# RS232.net
KiCad netlist of a schematic drawn in Altium Designer
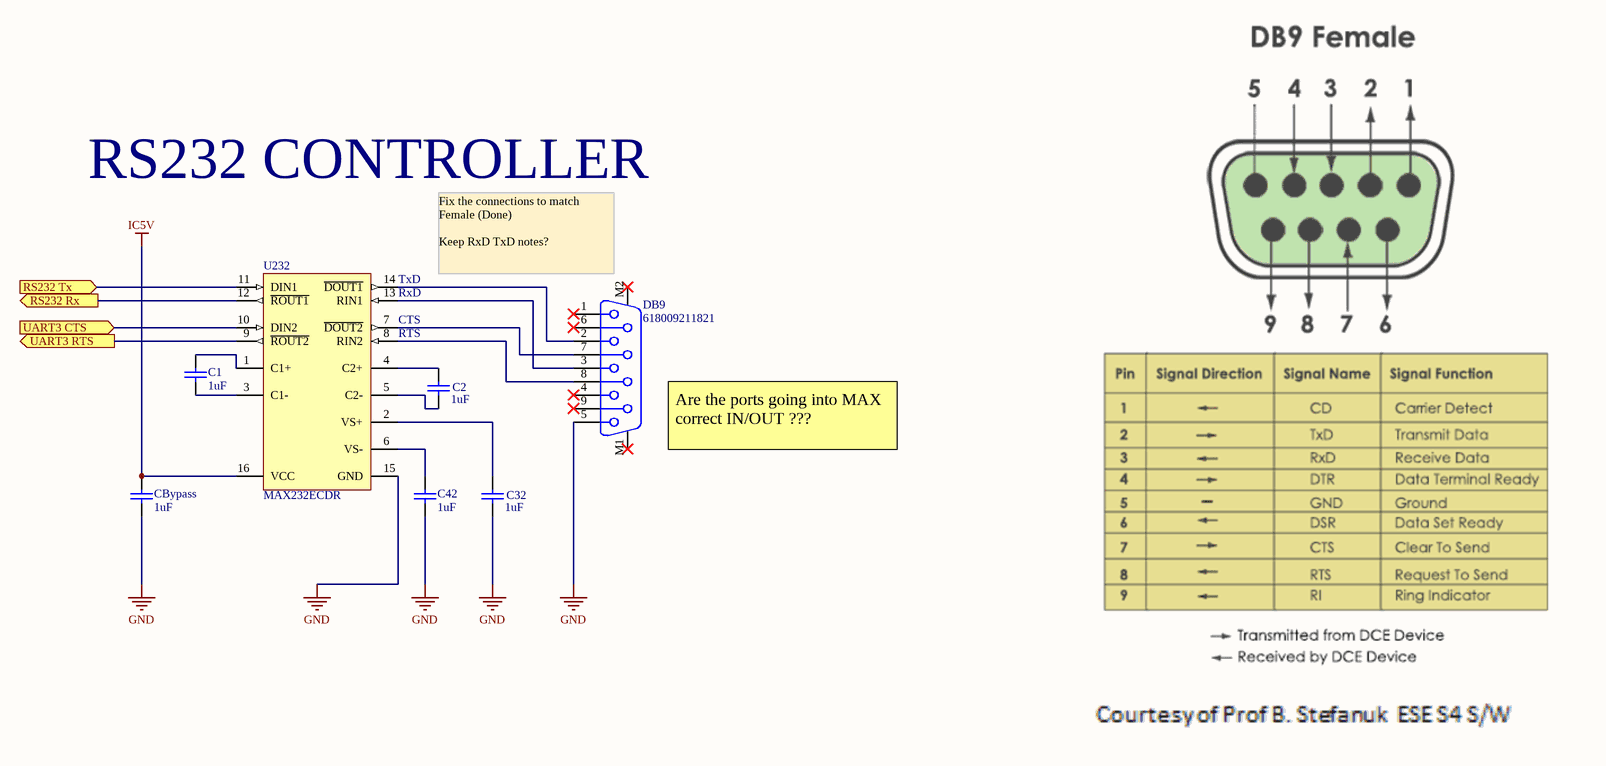
[diagram p0: RS232.SchDoc]

(export (version "E")
  (design (tool "Eeschema 10.0.6"))
  (components
    (comp (ref "C1")
      (value "1uF")
      (description "Capacitor")
      (libsource (lib "Simulation Generic Components") (part "Capacitor"))
    )
    (comp (ref "C2")
      (value "1uF")
      (description "Capacitor")
      (libsource (lib "Simulation Generic Components") (part "Capacitor"))
    )
    (comp (ref "C32")
      (value "1uF")
      (description "Capacitor")
      (libsource (lib "Simulation Generic Components") (part "Capacitor"))
    )
    (comp (ref "C42")
      (value "1uF")
      (description "Capacitor")
      (libsource (lib "Simulation Generic Components") (part "Capacitor"))
    )
    (comp (ref "CBypass")
      (value "1uF")
      (description "Capacitor")
      (libsource (lib "Simulation Generic Components") (part "Capacitor"))
    )
    (comp (ref "DB9")
      (value "618009211821")
      (footprint "618009211821")
      (libsource (lib "Altium Content Vault") (part "D-Sub_Female_09p"))
    )
    (comp (ref "U232")
      (value "MAX232ECDR")
      (footprint "D0016A_L")
      (libsource (lib "Altium Content Vault") (part "TI-MAX232E-SOIC_D-16"))
    )
  )
  (nets
    (net (code "1") (name "/RS232 Rx") (class "Default")
      (node (ref "U232") (pin "12") (pinfunction "~{ROUT1}_12") (pintype "output"))
    )
    (net (code "2") (name "/RS232 Tx") (class "Default")
      (node (ref "U232") (pin "11") (pinfunction "DIN1_11") (pintype "input"))
    )
    (net (code "3") (name "/UART3 CTS") (class "Default")
      (node (ref "U232") (pin "10") (pinfunction "DIN2_10") (pintype "input"))
    )
    (net (code "4") (name "/UART3 RTS") (class "Default")
      (node (ref "U232") (pin "9") (pinfunction "~{ROUT2}_9") (pintype "output"))
    )
    (net (code "5") (name "GND") (class "Default")
      (node (ref "C32") (pin "1") (pinfunction "1_1") (pintype "passive"))
      (node (ref "C42") (pin "1") (pinfunction "1_1") (pintype "passive"))
      (node (ref "CBypass") (pin "1") (pinfunction "1_1") (pintype "passive"))
      (node (ref "DB9") (pin "5") (pinfunction "5_5") (pintype "passive"))
      (node (ref "U232") (pin "15") (pinfunction "GND_15") (pintype "power_in"))
    )
    (net (code "6") (name "IC5V") (class "Default")
      (node (ref "CBypass") (pin "2") (pinfunction "2_2") (pintype "passive"))
      (node (ref "U232") (pin "16") (pinfunction "VCC_16") (pintype "power_in"))
    )
    (net (code "7") (name "Net-(U232-C1+)") (class "Default")
      (node (ref "C1") (pin "2") (pinfunction "2_2") (pintype "passive"))
      (node (ref "U232") (pin "1") (pinfunction "C1+_1") (pintype "passive"))
    )
    (net (code "8") (name "Net-(U232-C1-)") (class "Default")
      (node (ref "C1") (pin "1") (pinfunction "1_1") (pintype "passive"))
      (node (ref "U232") (pin "3") (pinfunction "C1-_3") (pintype "passive"))
    )
    (net (code "9") (name "Net-(U232-C2+)") (class "Default")
      (node (ref "C2") (pin "2") (pinfunction "2_2") (pintype "passive"))
      (node (ref "U232") (pin "4") (pinfunction "C2+_4") (pintype "passive"))
    )
    (net (code "10") (name "Net-(U232-C2-)") (class "Default")
      (node (ref "C2") (pin "1") (pinfunction "1_1") (pintype "passive"))
      (node (ref "U232") (pin "5") (pinfunction "C2-_5") (pintype "passive"))
    )
    (net (code "11") (name "Net-(U232-RIN1)") (class "Default")
      (node (ref "DB9") (pin "3") (pinfunction "3_3") (pintype "passive"))
      (node (ref "U232") (pin "13") (pinfunction "RIN1_13") (pintype "input"))
    )
    (net (code "12") (name "Net-(U232-RIN2)") (class "Default")
      (node (ref "DB9") (pin "8") (pinfunction "8_8") (pintype "passive"))
      (node (ref "U232") (pin "8") (pinfunction "RIN2_8") (pintype "input"))
    )
    (net (code "13") (name "Net-(U232-VS+)") (class "Default")
      (node (ref "C32") (pin "2") (pinfunction "2_2") (pintype "passive"))
      (node (ref "U232") (pin "2") (pinfunction "VS+_2") (pintype "power_in"))
    )
    (net (code "14") (name "Net-(U232-VS-)") (class "Default")
      (node (ref "C42") (pin "2") (pinfunction "2_2") (pintype "passive"))
      (node (ref "U232") (pin "6") (pinfunction "VS-_6") (pintype "power_in"))
    )
    (net (code "15") (name "Net-(U232-~{DOUT1})") (class "Default")
      (node (ref "DB9") (pin "2") (pinfunction "2_2") (pintype "passive"))
      (node (ref "U232") (pin "14") (pinfunction "~{DOUT1}_14") (pintype "output"))
    )
    (net (code "16") (name "Net-(U232-~{DOUT2})") (class "Default")
      (node (ref "DB9") (pin "7") (pinfunction "7_7") (pintype "passive"))
      (node (ref "U232") (pin "7") (pinfunction "~{DOUT2}_7") (pintype "output"))
    )
    (net (code "17") (name "unconnected-(DB9-Pad1)") (class "Default")
      (node (ref "DB9") (pin "1") (pinfunction "1_1") (pintype "passive+no_connect"))
    )
    (net (code "18") (name "unconnected-(DB9-Pad4)") (class "Default")
      (node (ref "DB9") (pin "4") (pinfunction "4_4") (pintype "passive+no_connect"))
    )
    (net (code "19") (name "unconnected-(DB9-Pad6)") (class "Default")
      (node (ref "DB9") (pin "6") (pinfunction "6_6") (pintype "passive+no_connect"))
    )
    (net (code "20") (name "unconnected-(DB9-Pad9)") (class "Default")
      (node (ref "DB9") (pin "9") (pinfunction "9_9") (pintype "passive+no_connect"))
    )
    (net (code "21") (name "unconnected-(DB9-PadM1)") (class "Default")
      (node (ref "DB9") (pin "M1") (pinfunction "M1_M1") (pintype "passive+no_connect"))
    )
    (net (code "22") (name "unconnected-(DB9-PadM2)") (class "Default")
      (node (ref "DB9") (pin "M2") (pinfunction "M2_M2") (pintype "passive+no_connect"))
    )
  )
)
